# ESPSwitchBoard.net
KiCad netlist of a schematic drawn in EAGLE
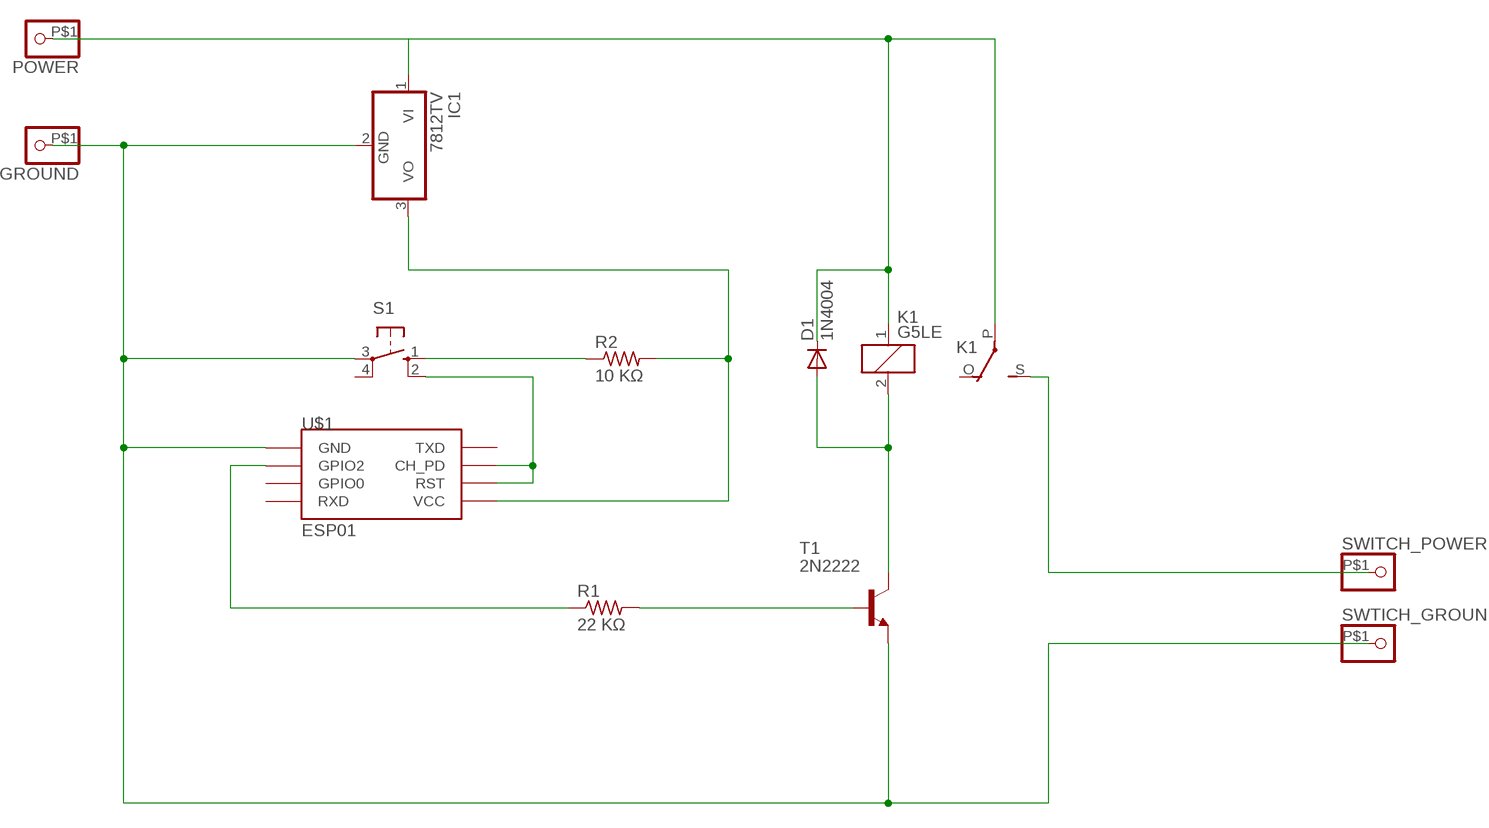
[diagram p0: schematic, sheet 1]

(export (version "E")
  (design (tool "Eeschema 10.0.6"))
  (components
    (comp (ref "D1")
      (value "1N4004")
      (footprint "eagle-import:DO41-10")
      (libsource (lib "eagle-import") (part "1N4004"))
    )
    (comp (ref "GROUND")
      (value "PINHD-1X1-BIGPOGO")
      (footprint "eagle-import:1X1-BIGPOGO")
      (libsource (lib "eagle-import") (part "PINHD-1X1-BIGPOGO"))
    )
    (comp (ref "IC1")
      (value "7812TV")
      (footprint "eagle-import:TO220V")
      (libsource (lib "eagle-import") (part "78TV12"))
    )
    (comp (ref "K1")
      (value "G5LE")
      (footprint "eagle-import:G5LE")
      (libsource (lib "eagle-import") (part "G5LE"))
    )
    (comp (ref "POWER")
      (value "PINHD-1X1-BIGPOGO")
      (footprint "eagle-import:1X1-BIGPOGO")
      (libsource (lib "eagle-import") (part "PINHD-1X1-BIGPOGO"))
    )
    (comp (ref "R1")
      (value "22 KΩ")
      (footprint "eagle-import:0805-THM")
      (libsource (lib "eagle-import") (part "FLIPFLOP-RES"))
    )
    (comp (ref "R2")
      (value "10 KΩ")
      (footprint "eagle-import:0805-THM")
      (libsource (lib "eagle-import") (part "FLIPFLOP-RES"))
    )
    (comp (ref "S1")
      (value "10-XX")
      (footprint "eagle-import:B3F-10XX")
      (fields (field (name "MPN") "B3F-1000"))
      (libsource (lib "eagle-import") (part "10-XX"))
    )
    (comp (ref "SWITCH_POWER")
      (value "PINHD-1X1-BIGPOGO")
      (footprint "eagle-import:1X1-BIGPOGO")
      (libsource (lib "eagle-import") (part "PINHD-1X1-BIGPOGO"))
    )
    (comp (ref "SWTICH_GROUND")
      (value "PINHD-1X1-BIGPOGO")
      (footprint "eagle-import:1X1-BIGPOGO")
      (libsource (lib "eagle-import") (part "PINHD-1X1-BIGPOGO"))
    )
    (comp (ref "T1")
      (value "2N2222")
      (footprint "eagle-import:TO92-EBC-OVAL")
      (libsource (lib "eagle-import") (part "2N2222"))
    )
    (comp (ref "U$1")
      (value "ESP01")
      (footprint "eagle-import:ESP01")
      (libsource (lib "eagle-import") (part "ESP01"))
    )
  )
  (nets
    (net (code "1") (name "Net-(D1-PadA)") (class "Default")
      (node (ref "D1") (pin "A") (pinfunction "A_A") (pintype "passive"))
      (node (ref "K1") (pin "2") (pinfunction "2_2") (pintype "passive"))
      (node (ref "T1") (pin "C") (pinfunction "C_C") (pintype "passive"))
    )
    (net (code "2") (name "Net-(GROUND-1)") (class "Default")
      (node (ref "GROUND") (pin "P$1") (pinfunction "1_P$1") (pintype "passive"))
      (node (ref "IC1") (pin "2") (pinfunction "GND_2") (pintype "passive"))
      (node (ref "S1") (pin "3") (pinfunction "P_3") (pintype "passive"))
      (node (ref "SWTICH_GROUND") (pin "P$1") (pinfunction "1_P$1") (pintype "passive"))
      (node (ref "T1") (pin "E") (pinfunction "E_E") (pintype "passive"))
      (node (ref "U$1") (pin "GND") (pinfunction "GND_GND") (pintype "bidirectional"))
    )
    (net (code "3") (name "Net-(IC1-VI)") (class "Default")
      (node (ref "D1") (pin "C") (pinfunction "C_C") (pintype "passive"))
      (node (ref "IC1") (pin "1") (pinfunction "VI_1") (pintype "input"))
      (node (ref "K1") (pin "1") (pinfunction "1_1") (pintype "passive"))
      (node (ref "K1") (pin "P") (pinfunction "P_P") (pintype "passive"))
      (node (ref "POWER") (pin "P$1") (pinfunction "1_P$1") (pintype "passive"))
    )
    (net (code "4") (name "Net-(IC1-VO)") (class "Default")
      (node (ref "IC1") (pin "3") (pinfunction "VO_3") (pintype "passive"))
      (node (ref "R2") (pin "2") (pinfunction "2_2") (pintype "passive"))
      (node (ref "U$1") (pin "VCC") (pinfunction "VCC_VCC") (pintype "bidirectional"))
    )
    (net (code "5") (name "Net-(R1-Pad1)") (class "Default")
      (node (ref "R1") (pin "1") (pinfunction "1_1") (pintype "passive"))
      (node (ref "U$1") (pin "GPIO2") (pinfunction "GPIO2_GPIO2") (pintype "bidirectional"))
    )
    (net (code "6") (name "Net-(R1-Pad2)") (class "Default")
      (node (ref "R1") (pin "2") (pinfunction "2_2") (pintype "passive"))
      (node (ref "T1") (pin "B") (pinfunction "B_B") (pintype "passive"))
    )
    (net (code "7") (name "Net-(S1-S)") (class "Default")
      (node (ref "R2") (pin "1") (pinfunction "1_1") (pintype "passive"))
      (node (ref "S1") (pin "1") (pinfunction "S_1") (pintype "passive"))
    )
    (net (code "8") (name "Net-(S1-S1)") (class "Default")
      (node (ref "S1") (pin "2") (pinfunction "S1_2") (pintype "passive"))
      (node (ref "U$1") (pin "CH_PD") (pinfunction "CH_PD_CH_PD") (pintype "bidirectional"))
      (node (ref "U$1") (pin "RST") (pinfunction "RST_RST") (pintype "bidirectional"))
    )
    (net (code "9") (name "Net-(SWITCH_POWER-1)") (class "Default")
      (node (ref "K1") (pin "S") (pinfunction "S_S") (pintype "passive"))
      (node (ref "SWITCH_POWER") (pin "P$1") (pinfunction "1_P$1") (pintype "passive"))
    )
    (net (code "10") (name "unconnected-(K1-PadO)") (class "Default")
      (node (ref "K1") (pin "O") (pinfunction "O_O") (pintype "passive"))
    )
    (net (code "11") (name "unconnected-(S1-P1-Pad4)") (class "Default")
      (node (ref "S1") (pin "4") (pinfunction "P1_4") (pintype "passive"))
    )
    (net (code "12") (name "unconnected-(U$1-PadGPIO0)") (class "Default")
      (node (ref "U$1") (pin "GPIO0") (pinfunction "GPIO0_GPIO0") (pintype "bidirectional"))
    )
    (net (code "13") (name "unconnected-(U$1-RXD-PadRX)") (class "Default")
      (node (ref "U$1") (pin "RX") (pinfunction "RXD_RX") (pintype "bidirectional"))
    )
    (net (code "14") (name "unconnected-(U$1-TXD-PadTX)") (class "Default")
      (node (ref "U$1") (pin "TX") (pinfunction "TXD_TX") (pintype "bidirectional"))
    )
  )
)
